# POWER.net
KiCad netlist of a schematic drawn in Altium Designer
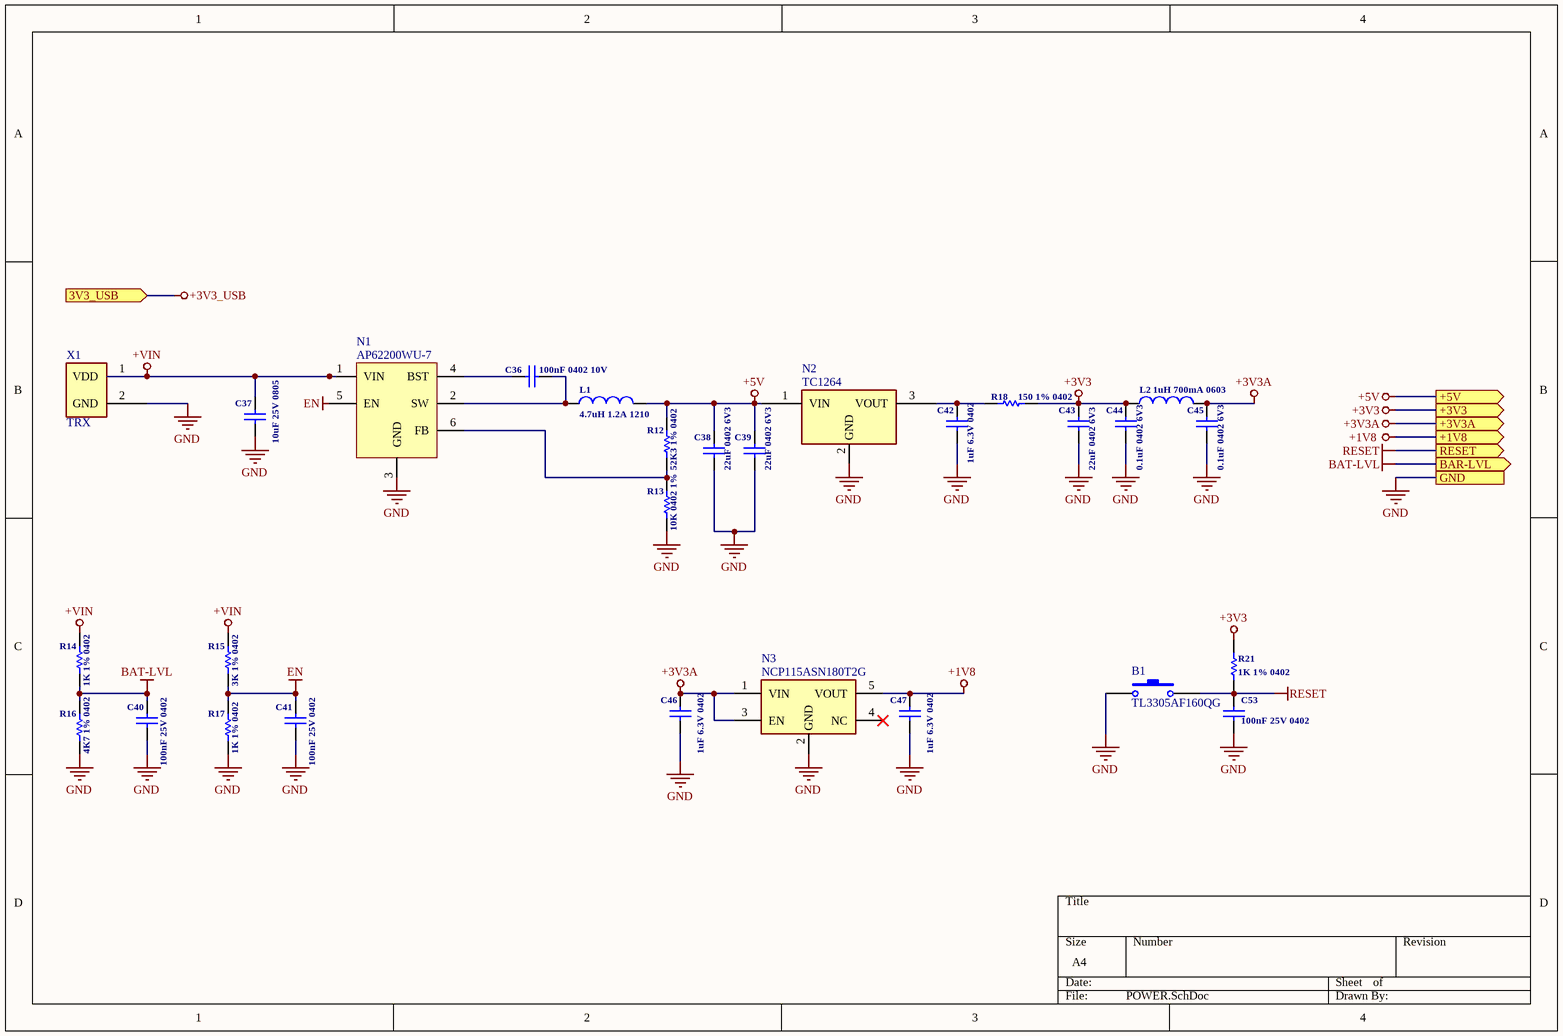
[diagram p0: POWER.SchDoc]

(export (version "E")
  (design (tool "Eeschema 10.0.6"))
  (components
    (comp (ref "B1")
      (value "TL3305AF160QG")
      (description "Tactile Switch SPST-NO Top Actuated Surface Mount")
      (libsource (lib "GenericButtons") (part "TL3305AF160QG"))
    )
    (comp (ref "C36")
      (value "100nF 0402 10V")
      (description "Cap Ceramic 0.1uF 10V X5R 10% SMD 0402 85C Paper T/R")
      (fields
        (field (name "MANUFACTURER") "Samsung")
        (field (name "MANUFACTURER PART NUMBER") "CL05A104KP5NNNC")
      )
      (libsource (lib "CondensadoresGenericos") (part "CL05A104KP5NNNC 100nF 0402 10V"))
    )
    (comp (ref "C37")
      (value "10uF 25V 0805")
      (description "10 µF ±10% 25V Ceramic Capacitor X5R 0805 (2012 Metric)")
      (libsource (lib "CondensadoresGenericos") (part "CL21A106KAYNNNG 10uF 0805"))
    )
    (comp (ref "C38")
      (value "22uF 0402 6V3")
      (description "CL05 Series 22 uF 6.3 V ±20% Tolerance X5R SMT Multilayer Ceramic Capacitor")
      (fields
        (field (name "MANUFACTURER") "Samsung")
        (field (name "MANUFACTURER PART NUMBER") "CL05A226MQ5N6J8")
      )
      (libsource (lib "CondensadoresGenericos") (part "CL05A226MQ5N6J8 22uF 0402 6V3"))
    )
    (comp (ref "C39")
      (value "22uF 0402 6V3")
      (description "CL05 Series 22 uF 6.3 V ±20% Tolerance X5R SMT Multilayer Ceramic Capacitor")
      (fields
        (field (name "MANUFACTURER") "Samsung")
        (field (name "MANUFACTURER PART NUMBER") "CL05A226MQ5N6J8")
      )
      (libsource (lib "CondensadoresGenericos") (part "CL05A226MQ5N6J8 22uF 0402 6V3"))
    )
    (comp (ref "C40")
      (value "100nF 25V 0402")
      (description "100nF, 25V, MLCC, 0402")
      (fields
        (field (name "MANUFACTURER") "Samsung")
        (field (name "MANUFACTURER PART NUMBER") "CL05A104KA5NNNC")
      )
      (libsource (lib "CondensadoresGenericos") (part "CL05A104KA5NNNC 100nf 0402"))
    )
    (comp (ref "C41")
      (value "100nF 25V 0402")
      (description "100nF, 25V, MLCC, 0402")
      (fields
        (field (name "MANUFACTURER") "Samsung")
        (field (name "MANUFACTURER PART NUMBER") "CL05A104KA5NNNC")
      )
      (libsource (lib "CondensadoresGenericos") (part "CL05A104KA5NNNC 100nf 0402"))
    )
    (comp (ref "C42")
      (value "1uF 6.3V 0402")
      (fields
        (field (name "MANUFACTURER") "Samsung")
        (field (name "MANUFACTURER PART NUMBER") "CL05A105KQ5NNNC")
      )
      (libsource (lib "CondensadoresGenericos") (part "CL05A105KQ5NNNC 1uF 0402"))
    )
    (comp (ref "C43")
      (value "22uF 0402 6V3")
      (description "CL05 Series 22 uF 6.3 V ±20% Tolerance X5R SMT Multilayer Ceramic Capacitor")
      (fields
        (field (name "MANUFACTURER") "Samsung")
        (field (name "MANUFACTURER PART NUMBER") "CL05A226MQ5N6J8")
      )
      (libsource (lib "CondensadoresGenericos") (part "CL05A226MQ5N6J8 22uF 0402 6V3"))
    )
    (comp (ref "C44")
      (value "0.1uF 0402 6V3")
      (description "0.1 µF ±10% 6.3V Ceramic Capacitor X7R 0402 (1005 Metric)")
      (libsource (lib "CondensadoresGenericos") (part "CL05B104KQ5NNNC 0.1uF 0402 6V3"))
    )
    (comp (ref "C45")
      (value "0.1uF 0402 6V3")
      (description "0.1 µF ±10% 6.3V Ceramic Capacitor X7R 0402 (1005 Metric)")
      (libsource (lib "CondensadoresGenericos") (part "CL05B104KQ5NNNC 0.1uF 0402 6V3"))
    )
    (comp (ref "C46")
      (value "1uF 6.3V 0402")
      (fields
        (field (name "MANUFACTURER") "Samsung")
        (field (name "MANUFACTURER PART NUMBER") "CL05A105KQ5NNNC")
      )
      (libsource (lib "CondensadoresGenericos") (part "CL05A105KQ5NNNC 1uF 0402"))
    )
    (comp (ref "C47")
      (value "1uF 6.3V 0402")
      (fields
        (field (name "MANUFACTURER") "Samsung")
        (field (name "MANUFACTURER PART NUMBER") "CL05A105KQ5NNNC")
      )
      (libsource (lib "CondensadoresGenericos") (part "CL05A105KQ5NNNC 1uF 0402"))
    )
    (comp (ref "C53")
      (value "100nF 25V 0402")
      (description "100nF, 25V, MLCC, 0402")
      (fields
        (field (name "MANUFACTURER") "Samsung")
        (field (name "MANUFACTURER PART NUMBER") "CL05A104KA5NNNC")
      )
      (libsource (lib "CondensadoresGenericos") (part "CL05A104KA5NNNC 100nf 0402"))
    )
    (comp (ref "L1")
      (value "4.7uH 1.2A 1210")
      (description "4.7 µH Shielded Wirewound Inductor 1.2 A 264mOhm Max 1210 (3225 Metric)")
      (libsource (lib "BobinasGenericas") (part "1276AS-H-4R7M=P2"))
    )
    (comp (ref "L2")
      (value "1uH 700mA 0603")
      (description "1 µH Shielded Multilayer Inductor 700 mA 110mOhm 0603 (1608 Metric)")
      (libsource (lib "BobinasGenericas") (part "MLZ1608N1R0LT000"))
    )
    (comp (ref "N1")
      (value "AP62200WU-7")
      (description "Buck Switching Regulator IC Positive Adjustable 0.8V 1 Output 2A SOT-23-6 Thin, TSOT-23-6")
      (libsource (lib "DIODE") (part "AP62200WU-7"))
    )
    (comp (ref "N2")
      (value "TC1264")
      (description "Linear Voltage Regulator IC Positive Fixed 1 Output 800mA SOT-223-3")
      (libsource (lib "Microchip_LDO") (part "TC1264-3.3VDBTR"))
    )
    (comp (ref "N3")
      (value "NCP115ASN180T2G")
      (footprint "NCP115ASN180T2G")
      (libsource (lib "Onsemi") (part "NCP115ASN180T2G"))
    )
    (comp (ref "R12")
      (value "52K3 1% 0402")
      (description "RES SMD 52.3K OHM 1% 1/16W 0402")
      (libsource (lib "ResistenciasGenericas") (part "RT0402FRE0752K3L 52K3 1% 0402"))
    )
    (comp (ref "R13")
      (value "10K 0402 1%")
      (footprint "Resistor_0402")
      (description "RES SMD 10K OHM 1% 1/16W 0402")
      (fields
        (field (name "MANUFACTURER") "Yageo")
        (field (name "MANUFACTURER PART NUMBER") "AC0402FR-0710KL")
      )
      (libsource (lib "ResistenciasGenericas") (part "AC0402FR-0710KL 10K 0402 1%"))
    )
    (comp (ref "R14")
      (value "1K 1% 0402")
      (footprint "Resistor_0402")
      (description "Res SMD 1 Kohm 1% 1/16W 0402")
      (fields
        (field (name "MANUFACTURER") "Cyntec")
        (field (name "MANUFACTURER PART NUMBER") "PFR05S-102-FNH")
      )
      (libsource (lib "ResistenciasGenericas") (part "PFR05S-102-FNH 1K 1% 0402"))
    )
    (comp (ref "R15")
      (value "3K 1% 0402")
      (description "3 kOhms ±1% 0.063W, 1/16W Chip Resistor 0402 (1005 Metric) Automotive AEC-Q200 Thick Film")
      (libsource (lib "ResistenciasGenericas") (part "RMCF0402FT3K00 3K 0402 1%"))
    )
    (comp (ref "R16")
      (value "4K7 1% 0402")
      (footprint "Resistor_0402")
      (description "Thick Film Resistors 1/16W 4.7K ohm 1% AEC-Q200")
      (fields
        (field (name "MANUFACTURER") "Yageo")
        (field (name "MANUFACTURER PART NUMBER") "AC0402FR-074K7L")
      )
      (libsource (lib "ResistenciasGenericas") (part "AC0402FR-074K7L 4.7K 1% 0402"))
    )
    (comp (ref "R17")
      (value "1K 1% 0402")
      (footprint "Resistor_0402")
      (description "Res SMD 1 Kohm 1% 1/16W 0402")
      (fields
        (field (name "MANUFACTURER") "Cyntec")
        (field (name "MANUFACTURER PART NUMBER") "PFR05S-102-FNH")
      )
      (libsource (lib "ResistenciasGenericas") (part "PFR05S-102-FNH 1K 1% 0402"))
    )
    (comp (ref "R18")
      (value "150 1% 0402")
      (description "150 Ohms ±1% 0.063W, 1/16W Chip Resistor 0402 (1005 Metric) Automotive AEC-Q200 Thick Film")
      (libsource (lib "ResistenciasGenericas") (part "RMCF0402FT150R 150 1% 0402"))
    )
    (comp (ref "R21")
      (value "1K 1% 0402")
      (footprint "Resistor_0402")
      (description "Res SMD 1 Kohm 1% 1/16W 0402")
      (fields
        (field (name "MANUFACTURER") "Cyntec")
        (field (name "MANUFACTURER PART NUMBER") "PFR05S-102-FNH")
      )
      (libsource (lib "ResistenciasGenericas") (part "PFR05S-102-FNH 1K 1% 0402"))
    )
    (comp (ref "X1") (value "TRX") (libsource (lib "Connectors") (part "TRX")))
  )
  (nets
    (net (code "1") (name "+1V8") (class "Default")
      (node (ref "C47") (pin "2") (pinfunction "2_2") (pintype "passive"))
      (node (ref "N3") (pin "5") (pinfunction "VOUT_5") (pintype "passive"))
    )
    (net (code "2") (name "+3V3") (class "Default")
      (node (ref "C43") (pin "2") (pinfunction "2_2") (pintype "passive"))
      (node (ref "C44") (pin "2") (pinfunction "2_2") (pintype "passive"))
      (node (ref "L2") (pin "1") (pinfunction "1_1") (pintype "passive"))
      (node (ref "R18") (pin "2") (pinfunction "2_2") (pintype "passive"))
      (node (ref "R21") (pin "2") (pinfunction "2_2") (pintype "passive"))
    )
    (net (code "3") (name "+3V3A") (class "Default")
      (node (ref "C45") (pin "2") (pinfunction "2_2") (pintype "passive"))
      (node (ref "C46") (pin "2") (pinfunction "2_2") (pintype "passive"))
      (node (ref "L2") (pin "2") (pinfunction "2_2") (pintype "passive"))
      (node (ref "N3") (pin "1") (pinfunction "VIN_1") (pintype "passive"))
      (node (ref "N3") (pin "3") (pinfunction "EN_3") (pintype "passive"))
    )
    (net (code "5") (name "+5V") (class "Default")
      (node (ref "C38") (pin "2") (pinfunction "2_2") (pintype "passive"))
      (node (ref "C39") (pin "2") (pinfunction "2_2") (pintype "passive"))
      (node (ref "L1") (pin "2") (pinfunction "2_2") (pintype "passive"))
      (node (ref "N2") (pin "1") (pinfunction "VIN_1") (pintype "passive"))
      (node (ref "R12") (pin "2") (pinfunction "2_2") (pintype "passive"))
    )
    (net (code "6") (name "+VIN") (class "Default")
      (node (ref "C37") (pin "2") (pinfunction "2_2") (pintype "passive"))
      (node (ref "N1") (pin "1") (pinfunction "VIN_1") (pintype "power_in"))
      (node (ref "R14") (pin "1") (pinfunction "1_1") (pintype "passive"))
      (node (ref "R15") (pin "2") (pinfunction "2_2") (pintype "passive"))
      (node (ref "X1") (pin "1") (pinfunction "VDD_1") (pintype "power_in"))
    )
    (net (code "7") (name "BAT-LVL") (class "Default")
      (node (ref "C40") (pin "2") (pinfunction "2_2") (pintype "passive"))
      (node (ref "R14") (pin "2") (pinfunction "2_2") (pintype "passive"))
      (node (ref "R16") (pin "2") (pinfunction "2_2") (pintype "passive"))
    )
    (net (code "8") (name "EN") (class "Default")
      (node (ref "C41") (pin "2") (pinfunction "2_2") (pintype "passive"))
      (node (ref "R15") (pin "1") (pinfunction "1_1") (pintype "passive"))
      (node (ref "R17") (pin "1") (pinfunction "1_1") (pintype "passive"))
    )
    (net (code "9") (name "GND") (class "Default")
      (node (ref "B1") (pin "1") (pinfunction "1_1") (pintype "passive"))
      (node (ref "C37") (pin "1") (pinfunction "1_1") (pintype "passive"))
      (node (ref "C38") (pin "1") (pinfunction "1_1") (pintype "passive"))
      (node (ref "C39") (pin "1") (pinfunction "1_1") (pintype "passive"))
      (node (ref "C40") (pin "1") (pinfunction "1_1") (pintype "passive"))
      (node (ref "C41") (pin "1") (pinfunction "1_1") (pintype "passive"))
      (node (ref "C42") (pin "1") (pinfunction "1_1") (pintype "passive"))
      (node (ref "C43") (pin "1") (pinfunction "1_1") (pintype "passive"))
      (node (ref "C44") (pin "1") (pinfunction "1_1") (pintype "passive"))
      (node (ref "C45") (pin "1") (pinfunction "1_1") (pintype "passive"))
      (node (ref "C46") (pin "1") (pinfunction "1_1") (pintype "passive"))
      (node (ref "C47") (pin "1") (pinfunction "1_1") (pintype "passive"))
      (node (ref "C53") (pin "1") (pinfunction "1_1") (pintype "passive"))
      (node (ref "N1") (pin "3") (pinfunction "GND_3") (pintype "power_in"))
      (node (ref "N2") (pin "2") (pinfunction "GND_2") (pintype "passive"))
      (node (ref "N3") (pin "2") (pinfunction "GND_2") (pintype "passive"))
      (node (ref "R13") (pin "1") (pinfunction "1_1") (pintype "passive"))
      (node (ref "R16") (pin "1") (pinfunction "1_1") (pintype "passive"))
      (node (ref "R17") (pin "2") (pinfunction "2_2") (pintype "passive"))
      (node (ref "X1") (pin "2") (pinfunction "GND_2") (pintype "power_in"))
    )
    (net (code "10") (name "Net-(N1-BST)") (class "Default")
      (node (ref "C36") (pin "2") (pinfunction "2_2") (pintype "passive"))
      (node (ref "N1") (pin "4") (pinfunction "BST_4") (pintype "power_in"))
    )
    (net (code "11") (name "Net-(N1-FB)") (class "Default")
      (node (ref "N1") (pin "6") (pinfunction "FB_6") (pintype "power_in"))
      (node (ref "R12") (pin "1") (pinfunction "1_1") (pintype "passive"))
      (node (ref "R13") (pin "2") (pinfunction "2_2") (pintype "passive"))
    )
    (net (code "12") (name "Net-(N1-SW)") (class "Default")
      (node (ref "C36") (pin "1") (pinfunction "1_1") (pintype "passive"))
      (node (ref "L1") (pin "1") (pinfunction "1_1") (pintype "passive"))
      (node (ref "N1") (pin "2") (pinfunction "SW_2") (pintype "power_in"))
    )
    (net (code "13") (name "Net-(N2-VOUT)") (class "Default")
      (node (ref "C42") (pin "2") (pinfunction "2_2") (pintype "passive"))
      (node (ref "N2") (pin "3") (pinfunction "VOUT_3") (pintype "passive"))
      (node (ref "R18") (pin "1") (pinfunction "1_1") (pintype "passive"))
    )
    (net (code "14") (name "RESET") (class "Default")
      (node (ref "B1") (pin "3") (pinfunction "2_3") (pintype "passive"))
      (node (ref "C53") (pin "2") (pinfunction "2_2") (pintype "passive"))
      (node (ref "R21") (pin "1") (pinfunction "1_1") (pintype "passive"))
    )
    (net (code "15") (name "unconnected-(N1-EN-Pad5)") (class "Default")
      (node (ref "N1") (pin "5") (pinfunction "EN_5") (pintype "power_in"))
    )
    (net (code "16") (name "unconnected-(N3-NC-Pad4)") (class "Default")
      (node (ref "N3") (pin "4") (pinfunction "NC_4") (pintype "passive+no_connect"))
    )
  )
)
